# 6-CONFIG.net
KiCad netlist of a schematic drawn in Altium Designer
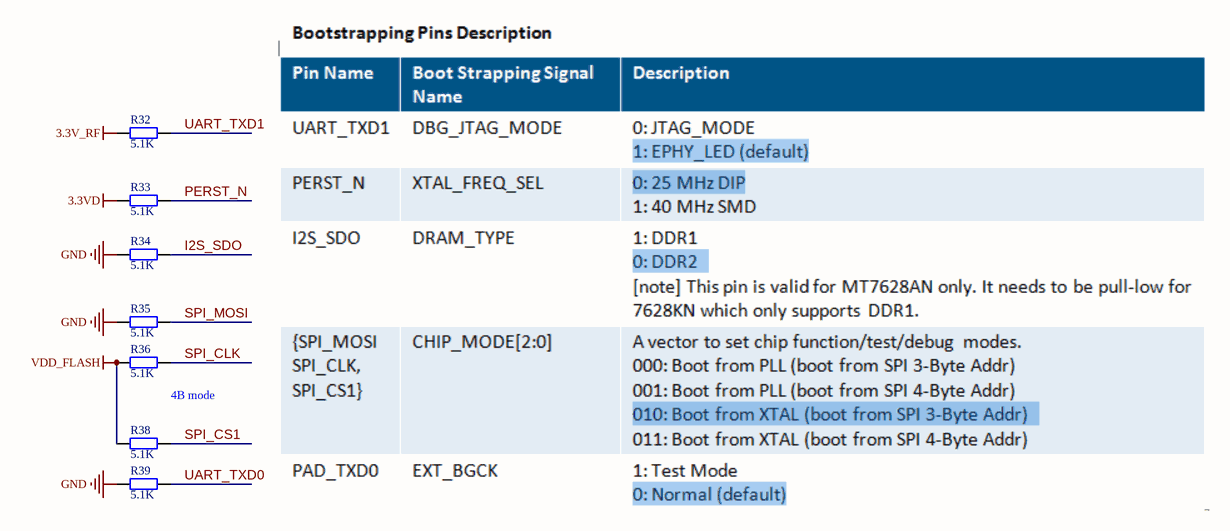
[diagram p0: 6-CONFIG.SchDoc]

(export (version "E")
  (design (tool "Eeschema 10.0.6"))
  (components
    (comp (ref "R32")
      (value "5.1K")
      (footprint "R0402")
      (description "普通电阻")
      (libsource (lib "LIB_MANGO") (part "RES"))
    )
    (comp (ref "R33")
      (value "5.1K")
      (footprint "R0402")
      (description "普通电阻")
      (libsource (lib "LIB_MANGO") (part "RES"))
    )
    (comp (ref "R34")
      (value "5.1K")
      (footprint "R0402")
      (description "普通电阻")
      (libsource (lib "LIB_MANGO") (part "RES"))
    )
    (comp (ref "R35")
      (value "5.1K")
      (footprint "R0402")
      (description "普通电阻")
      (libsource (lib "LIB_MANGO") (part "RES"))
    )
    (comp (ref "R36")
      (value "5.1K")
      (footprint "R0402")
      (description "普通电阻")
      (libsource (lib "LIB_MANGO") (part "RES"))
    )
    (comp (ref "R38")
      (value "5.1K")
      (footprint "R0402")
      (description "普通电阻")
      (libsource (lib "LIB_MANGO") (part "RES"))
    )
    (comp (ref "R39")
      (value "5.1K")
      (footprint "R0402")
      (description "普通电阻")
      (libsource (lib "LIB_MANGO") (part "RES"))
    )
  )
  (nets
    (net (code "1") (name "/I2S_SDO") (class "Default")
      (node (ref "R34") (pin "2") (pinfunction "2_2") (pintype "passive"))
    )
    (net (code "2") (name "/PERST_N") (class "Default")
      (node (ref "R33") (pin "2") (pinfunction "2_2") (pintype "passive"))
    )
    (net (code "3") (name "/SPI_CLK") (class "Default")
      (node (ref "R36") (pin "2") (pinfunction "2_2") (pintype "passive"))
    )
    (net (code "4") (name "/SPI_CS1") (class "Default")
      (node (ref "R38") (pin "2") (pinfunction "2_2") (pintype "passive"))
    )
    (net (code "5") (name "/SPI_MOSI") (class "Default")
      (node (ref "R35") (pin "2") (pinfunction "2_2") (pintype "passive"))
    )
    (net (code "6") (name "/UART_TXD0") (class "Default")
      (node (ref "R39") (pin "2") (pinfunction "2_2") (pintype "passive"))
    )
    (net (code "7") (name "/UART_TXD1") (class "Default")
      (node (ref "R32") (pin "2") (pinfunction "2_2") (pintype "passive"))
    )
    (net (code "8") (name "3.3VD") (class "Default")
      (node (ref "R33") (pin "1") (pinfunction "1_1") (pintype "passive"))
    )
    (net (code "9") (name "3.3V_RF") (class "Default")
      (node (ref "R32") (pin "1") (pinfunction "1_1") (pintype "passive"))
    )
    (net (code "10") (name "GND") (class "Default")
      (node (ref "R34") (pin "1") (pinfunction "1_1") (pintype "passive"))
      (node (ref "R35") (pin "1") (pinfunction "1_1") (pintype "passive"))
      (node (ref "R39") (pin "1") (pinfunction "1_1") (pintype "passive"))
    )
    (net (code "11") (name "VDD_FLASH") (class "Default")
      (node (ref "R36") (pin "1") (pinfunction "1_1") (pintype "passive"))
      (node (ref "R38") (pin "1") (pinfunction "1_1") (pintype "passive"))
    )
  )
)
